# cond_sinais.net
KiCad netlist of a schematic drawn in Altium Designer
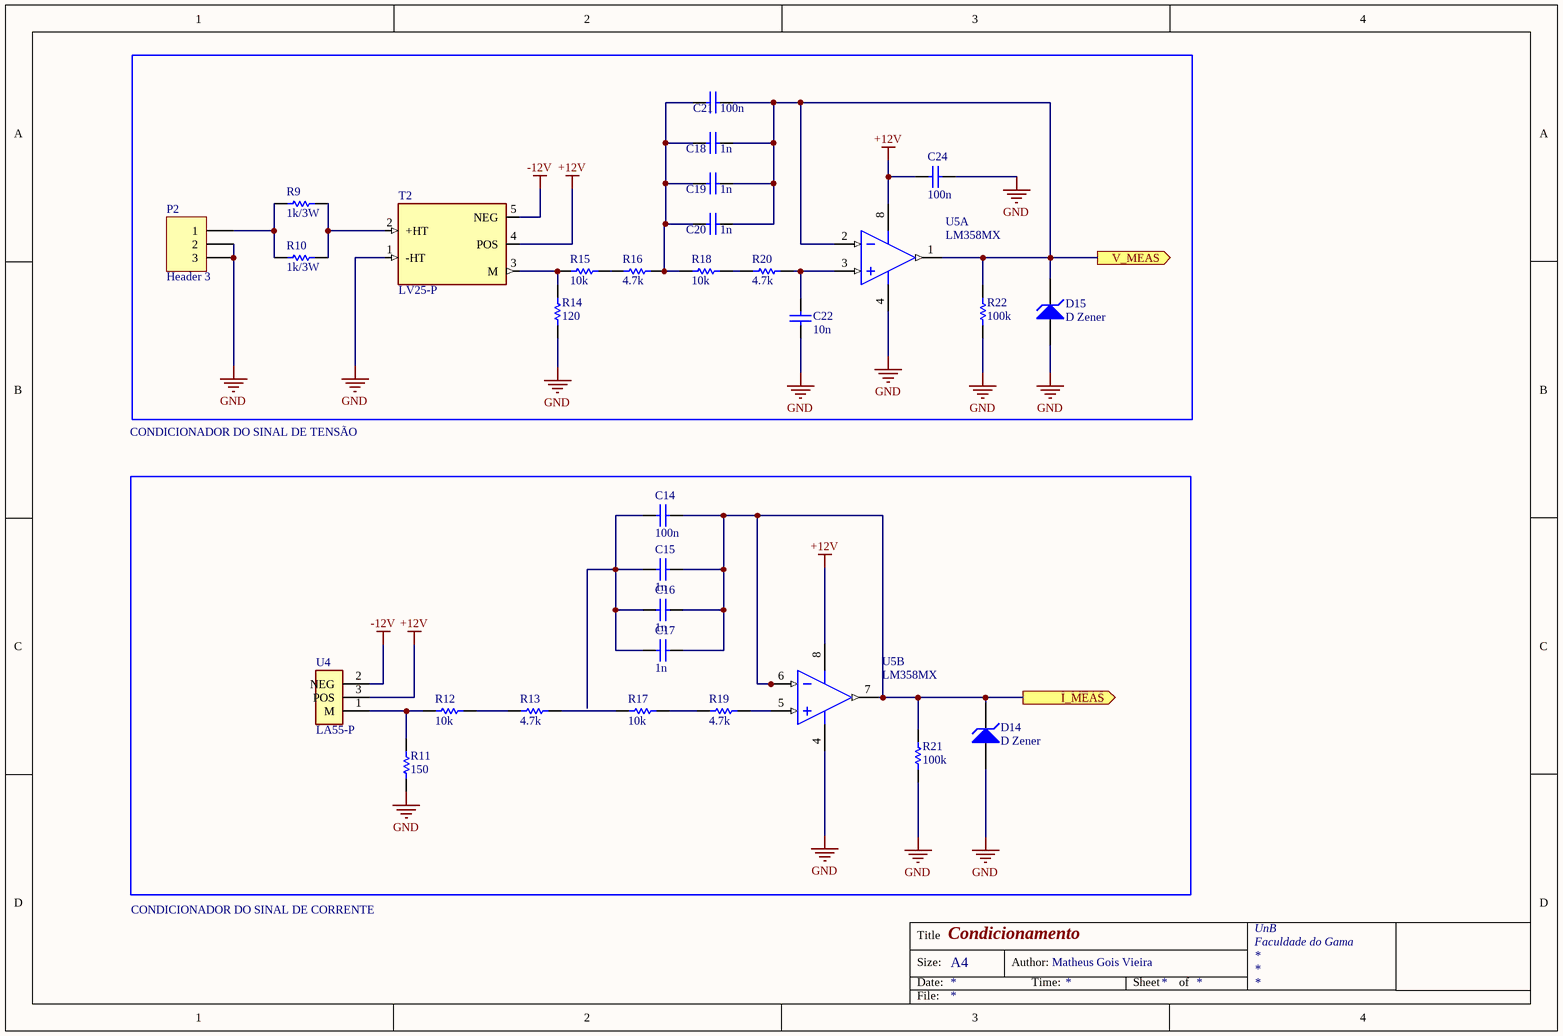
[diagram p0: cond_sinais.SchDoc]

(export (version "E")
  (design (tool "Eeschema 10.0.6"))
  (components
    (comp (ref "C14")
      (value "100n")
      (footprint "C0603[0201]")
      (description "CAP CER 10000PF 50V X7R 0603")
      (fields (field (name "MANUFACTURER PART NUMBER") "C0603C103K5RACTU") (field (name "TOLERANCE") "10%"))
      (libsource (lib "Basic Library") (part "C"))
    )
    (comp (ref "C15")
      (value "1n")
      (footprint "C0603[0201]")
      (description "Cap Ceramic 0.001uF 50V X7R 10% SMD 0603 125C T/R")
      (fields (field (name "MANUFACTURER PART NUMBER") "C0603C102K5RACTU") (field (name "TOLERANCE") "10%"))
      (libsource (lib "Basic Library") (part "C"))
    )
    (comp (ref "C16")
      (value "1n")
      (footprint "C0603[0201]")
      (description "Cap Ceramic 0.001uF 50V X7R 10% SMD 0603 125C T/R")
      (fields (field (name "MANUFACTURER PART NUMBER") "C0603C102K5RACTU") (field (name "TOLERANCE") "10%"))
      (libsource (lib "Basic Library") (part "C"))
    )
    (comp (ref "C17")
      (value "1n")
      (footprint "C0603[0201]")
      (description "Cap Ceramic 0.001uF 50V X7R 10% SMD 0603 125C T/R")
      (fields (field (name "MANUFACTURER PART NUMBER") "C0603C102K5RACTU") (field (name "TOLERANCE") "10%"))
      (libsource (lib "Basic Library") (part "C"))
    )
    (comp (ref "C18")
      (value "1n")
      (footprint "C0603[0201]")
      (description "Cap Ceramic 0.001uF 50V X7R 10% SMD 0603 125C T/R")
      (fields (field (name "MANUFACTURER PART NUMBER") "C0603C102K5RACTU") (field (name "TOLERANCE") "10%"))
      (libsource (lib "Basic Library") (part "C"))
    )
    (comp (ref "C19")
      (value "1n")
      (footprint "C0603[0201]")
      (description "Cap Ceramic 0.001uF 50V X7R 10% SMD 0603 125C T/R")
      (fields (field (name "MANUFACTURER PART NUMBER") "C0603C102K5RACTU") (field (name "TOLERANCE") "10%"))
      (libsource (lib "Basic Library") (part "C"))
    )
    (comp (ref "C20")
      (value "1n")
      (footprint "C0603[0201]")
      (description "Cap Ceramic 0.001uF 50V X7R 10% SMD 0603 125C T/R")
      (fields (field (name "MANUFACTURER PART NUMBER") "C0603C102K5RACTU") (field (name "TOLERANCE") "10%"))
      (libsource (lib "Basic Library") (part "C"))
    )
    (comp (ref "C21")
      (value "100n")
      (footprint "C0603[0201]")
      (description "CAP CER 10000PF 50V X7R 0603")
      (fields (field (name "MANUFACTURER PART NUMBER") "C0603C103K5RACTU") (field (name "TOLERANCE") "10%"))
      (libsource (lib "Basic Library") (part "C"))
    )
    (comp (ref "C22")
      (value "10n")
      (footprint "C0603[0201]")
      (description "CAP CER 10000PF 50V X7R 0603")
      (fields (field (name "MANUFACTURER PART NUMBER") "C0603C103K5RACTU") (field (name "TOLERANCE") "10%"))
      (libsource (lib "Basic Library") (part "C"))
    )
    (comp (ref "C24")
      (value "100n")
      (footprint "C0603[0201]")
      (description "贴片陶瓷电容 0.1uF ±10% 50V X7R 0603")
      (fields (field (name "MANUFACTURER PART NUMBER") "C0603C104K5RACTU") (field (name "TOLERANCE") "10%"))
      (libsource (lib "Basic Library") (part "C"))
    )
    (comp (ref "D14")
      (value "D Zener")
      (footprint "DIODE-SIGNAL")
      (description "Diode Zener Single 9.1V 5% 500mW 2-Pin(1+Tab) Power Mite T/R")
      (fields (field (name "MANUFACTURER PART NUMBER") "1PMT5924BT1G") (field (name "TOLERANCE") "5%"))
      (libsource (lib "Basic Library") (part "D Zener"))
    )
    (comp (ref "D15")
      (value "D Zener")
      (footprint "DIODE-SIGNAL")
      (description "Diode Zener Single 9.1V 5% 500mW 2-Pin(1+Tab) Power Mite T/R")
      (fields (field (name "MANUFACTURER PART NUMBER") "1PMT5924BT1G") (field (name "TOLERANCE") "5%"))
      (libsource (lib "Basic Library") (part "D Zener"))
    )
    (comp (ref "P2")
      (value "Header 3")
      (footprint "HDR1X3")
      (description "Header, 3-Pin")
      (fields (field (name "PUBLISHER") "Altium Limited"))
      (libsource (lib "Miscellaneous Connectors") (part "Header 3"))
    )
    (comp (ref "R9")
      (value "1k/3W")
      (footprint "R1005[0402]")
      (description "Res Thick Film 2512 1K Ohm 5% 3W ±100ppm/C Pad SMD T/R")
      (fields (field (name "MANUFACTURER PART NUMBER") "35221K0JT") (field (name "TOLERANCE") "5%"))
      (libsource (lib "Basic Library") (part "R"))
    )
    (comp (ref "R10")
      (value "1k/3W")
      (footprint "R1005[0402]")
      (description "Res Thick Film 2512 1K Ohm 5% 3W ±100ppm/C Pad SMD T/R")
      (fields (field (name "MANUFACTURER PART NUMBER") "35221K0JT") (field (name "TOLERANCE") "5%"))
      (libsource (lib "Basic Library") (part "R"))
    )
    (comp (ref "R11")
      (value "150")
      (footprint "R1005[0402]")
      (description "贴片电阻 150Ω ±1% 1/4W ±100ppm/℃ 1206")
      (fields (field (name "MANUFACTURER PART NUMBER") "ERJ-8ENF1500V") (field (name "TOLERANCE") "1%"))
      (libsource (lib "Basic Library") (part "R"))
    )
    (comp (ref "R12")
      (value "10k")
      (footprint "R1608[0603]")
      (description "Res, 10K, 0.01%, 0.25W, 1206, Metal Foil")
      (fields (field (name "MANUFACTURER PART NUMBER") "Y163010K0000T9R") (field (name "TOLERANCE") "0.01%"))
      (libsource (lib "Basic Library") (part "R"))
    )
    (comp (ref "R13")
      (value "4.7k")
      (footprint "R1005[0402]")
      (description "Res Thick Film 1206 4.7K Ohm 5% 1/4W ±200ppm/°C Molded SMD Punched Carrier T/R")
      (fields (field (name "MANUFACTURER PART NUMBER") "ERJ-8GEYJ472V") (field (name "TOLERANCE") "5%"))
      (libsource (lib "Basic Library") (part "R"))
    )
    (comp (ref "R14")
      (value "120")
      (footprint "R1005[0402]")
      (description "Resistor Thick Film 1206 120 Ohm 5% 1/4W 200ppm/C Molded SMD Punched Carrier T/R")
      (fields (field (name "MANUFACTURER PART NUMBER") "ERJ-8GEYJ121V") (field (name "TOLERANCE") "5%"))
      (libsource (lib "Basic Library") (part "R"))
    )
    (comp (ref "R15")
      (value "10k")
      (footprint "R1608[0603]")
      (description "Res, 10K, 0.01%, 0.25W, 1206, Metal Foil")
      (fields (field (name "MANUFACTURER PART NUMBER") "Y163010K0000T9R") (field (name "TOLERANCE") "0.01%"))
      (libsource (lib "Basic Library") (part "R"))
    )
    (comp (ref "R16")
      (value "4.7k")
      (footprint "R1005[0402]")
      (description "Res Thick Film 1206 4.7K Ohm 5% 1/4W ±200ppm/°C Molded SMD Punched Carrier T/R")
      (fields (field (name "MANUFACTURER PART NUMBER") "ERJ-8GEYJ472V") (field (name "TOLERANCE") "5%"))
      (libsource (lib "Basic Library") (part "R"))
    )
    (comp (ref "R17")
      (value "10k")
      (footprint "R1005[0402]")
      (description "Res, 10K, 0.01%, 0.25W, 1206, Metal Foil")
      (fields (field (name "MANUFACTURER PART NUMBER") "Y163010K0000T9R") (field (name "TOLERANCE") "0.01%"))
      (libsource (lib "Basic Library") (part "R"))
    )
    (comp (ref "R18")
      (value "10k")
      (footprint "R1005[0402]")
      (description "Res, 10K, 0.01%, 0.25W, 1206, Metal Foil")
      (fields (field (name "MANUFACTURER PART NUMBER") "Y163010K0000T9R") (field (name "TOLERANCE") "0.01%"))
      (libsource (lib "Basic Library") (part "R"))
    )
    (comp (ref "R19")
      (value "4.7k")
      (footprint "R1005[0402]")
      (description "Res Thick Film 1206 4.7K Ohm 5% 1/4W ±200ppm/°C Molded SMD Punched Carrier T/R")
      (fields (field (name "MANUFACTURER PART NUMBER") "ERJ-8GEYJ472V") (field (name "TOLERANCE") "5%"))
      (libsource (lib "Basic Library") (part "R"))
    )
    (comp (ref "R20")
      (value "4.7k")
      (footprint "R1005[0402]")
      (description "Res Thick Film 1206 4.7K Ohm 5% 1/4W ±200ppm/°C Molded SMD Punched Carrier T/R")
      (fields (field (name "MANUFACTURER PART NUMBER") "ERJ-8GEYJ472V") (field (name "TOLERANCE") "5%"))
      (libsource (lib "Basic Library") (part "R"))
    )
    (comp (ref "R21")
      (value "100k")
      (footprint "R1005[0402]")
      (description "贴片电阻 100KΩ ±1% 1/4W ±100ppm/℃ 1206")
      (fields (field (name "MANUFACTURER PART NUMBER") "ERJ-8ENF1003V") (field (name "TOLERANCE") "1%"))
      (libsource (lib "Basic Library") (part "R"))
    )
    (comp (ref "R22")
      (value "100k")
      (footprint "R1005[0402]")
      (description "贴片电阻 100KΩ ±1% 1/4W ±100ppm/℃ 1206")
      (fields (field (name "MANUFACTURER PART NUMBER") "ERJ-8ENF1003V") (field (name "TOLERANCE") "1%"))
      (libsource (lib "Basic Library") (part "R"))
    )
    (comp (ref "T2")
      (value "LV25-P")
      (footprint "XDCR_LV25-P")
      (description "Hall Effect Voltage Transducer")
      (fields (field (name "DIGI-KEY_PART_NUMBER") "398-1019-ND") (field (name "MF") "LEM USA Inc."))
      (libsource (lib "LV25-P") (part "LV25-P"))
    )
    (comp (ref "U4")
      (value "LA55-P")
      (footprint "XDCR_LA55-P")
      (description "Current Sensor 50A 1 Channel Hall Effect, Closed Loop Bidirectional Module, Single Pass Through")
      (fields (field (name "MP") "LA 55-P") (field (name "MF") "LEM USA"))
      (libsource (lib "LA55-P") (part "LA55-P"))
    )
    (comp (ref "U5")
      (value "LM358MX")
      (footprint "M08A_N")
      (description "LM358 Series 7 mV Input Offset Dual Operational Amplifier - SOIC-8")
      (fields (field (name "MANUFACTURER") "National Semiconductor"))
      (libsource (lib "National Semiconductor Amplifier") (part "LM358MX"))
    )
  )
  (nets
    (net (code "1") (name "+12V") (class "Default")
      (node (ref "C24") (pin "2") (pinfunction "2_2") (pintype "passive"))
      (node (ref "T2") (pin "4") (pinfunction "POS_4") (pintype "power_in"))
      (node (ref "U4") (pin "3") (pinfunction "POS_3") (pintype "power_in"))
      (node (ref "U5") (pin "8") (pinfunction "V+_8") (pintype "power_in"))
    )
    (net (code "2") (name "-12V") (class "Default")
      (node (ref "T2") (pin "5") (pinfunction "NEG_5") (pintype "power_in"))
      (node (ref "U4") (pin "2") (pinfunction "NEG_2") (pintype "power_in"))
    )
    (net (code "3") (name "/I_MEAS") (class "Default")
      (node (ref "C14") (pin "2") (pinfunction "2_2") (pintype "passive"))
      (node (ref "C15") (pin "2") (pinfunction "2_2") (pintype "passive"))
      (node (ref "C16") (pin "2") (pinfunction "2_2") (pintype "passive"))
      (node (ref "C17") (pin "2") (pinfunction "2_2") (pintype "passive"))
      (node (ref "D14") (pin "2") (pinfunction "K_2") (pintype "passive"))
      (node (ref "R21") (pin "2") (pinfunction "2_2") (pintype "passive"))
      (node (ref "U5") (pin "6") (pinfunction "INB-_6") (pintype "input"))
      (node (ref "U5") (pin "7") (pinfunction "OUTB_7") (pintype "output"))
    )
    (net (code "4") (name "/V_MEAS") (class "Default")
      (node (ref "C18") (pin "2") (pinfunction "2_2") (pintype "passive"))
      (node (ref "C19") (pin "2") (pinfunction "2_2") (pintype "passive"))
      (node (ref "C20") (pin "2") (pinfunction "2_2") (pintype "passive"))
      (node (ref "C21") (pin "2") (pinfunction "2_2") (pintype "passive"))
      (node (ref "D15") (pin "2") (pinfunction "K_2") (pintype "passive"))
      (node (ref "R22") (pin "2") (pinfunction "2_2") (pintype "passive"))
      (node (ref "U5") (pin "1") (pinfunction "OUTA_1") (pintype "output"))
      (node (ref "U5") (pin "2") (pinfunction "INA-_2") (pintype "input"))
    )
    (net (code "5") (name "GND") (class "Default")
      (node (ref "C22") (pin "1") (pinfunction "1_1") (pintype "passive"))
      (node (ref "C24") (pin "1") (pinfunction "1_1") (pintype "passive"))
      (node (ref "D14") (pin "1") (pinfunction "A_1") (pintype "passive"))
      (node (ref "D15") (pin "1") (pinfunction "A_1") (pintype "passive"))
      (node (ref "P2") (pin "2") (pinfunction "2_2") (pintype "passive"))
      (node (ref "P2") (pin "3") (pinfunction "3_3") (pintype "passive"))
      (node (ref "R11") (pin "1") (pinfunction "1_1") (pintype "passive"))
      (node (ref "R14") (pin "1") (pinfunction "1_1") (pintype "passive"))
      (node (ref "R21") (pin "1") (pinfunction "1_1") (pintype "passive"))
      (node (ref "R22") (pin "1") (pinfunction "1_1") (pintype "passive"))
      (node (ref "T2") (pin "1") (pinfunction "-HT_1") (pintype "input"))
      (node (ref "U5") (pin "4") (pinfunction "GND_4") (pintype "power_in"))
    )
    (net (code "6") (name "Net-(C14-Pad1)") (class "Default")
      (node (ref "C14") (pin "1") (pinfunction "1_1") (pintype "passive"))
      (node (ref "C15") (pin "1") (pinfunction "1_1") (pintype "passive"))
      (node (ref "C16") (pin "1") (pinfunction "1_1") (pintype "passive"))
      (node (ref "C17") (pin "1") (pinfunction "1_1") (pintype "passive"))
    )
    (net (code "7") (name "Net-(C18-Pad1)") (class "Default")
      (node (ref "C18") (pin "1") (pinfunction "1_1") (pintype "passive"))
      (node (ref "C19") (pin "1") (pinfunction "1_1") (pintype "passive"))
      (node (ref "C20") (pin "1") (pinfunction "1_1") (pintype "passive"))
      (node (ref "C21") (pin "1") (pinfunction "1_1") (pintype "passive"))
      (node (ref "R16") (pin "2") (pinfunction "2_2") (pintype "passive"))
      (node (ref "R18") (pin "1") (pinfunction "1_1") (pintype "passive"))
    )
    (net (code "8") (name "Net-(P2-Pad1)") (class "Default")
      (node (ref "P2") (pin "1") (pinfunction "1_1") (pintype "passive"))
      (node (ref "R10") (pin "1") (pinfunction "1_1") (pintype "passive"))
      (node (ref "R9") (pin "1") (pinfunction "1_1") (pintype "passive"))
    )
    (net (code "9") (name "Net-(R12-Pad2)") (class "Default")
      (node (ref "R12") (pin "2") (pinfunction "2_2") (pintype "passive"))
      (node (ref "R13") (pin "1") (pinfunction "1_1") (pintype "passive"))
    )
    (net (code "10") (name "Net-(R13-Pad2)") (class "Default")
      (node (ref "R13") (pin "2") (pinfunction "2_2") (pintype "passive"))
      (node (ref "R17") (pin "1") (pinfunction "1_1") (pintype "passive"))
    )
    (net (code "11") (name "Net-(R15-Pad2)") (class "Default")
      (node (ref "R15") (pin "2") (pinfunction "2_2") (pintype "passive"))
      (node (ref "R16") (pin "1") (pinfunction "1_1") (pintype "passive"))
    )
    (net (code "12") (name "Net-(R17-Pad2)") (class "Default")
      (node (ref "R17") (pin "2") (pinfunction "2_2") (pintype "passive"))
      (node (ref "R19") (pin "1") (pinfunction "1_1") (pintype "passive"))
    )
    (net (code "13") (name "Net-(R18-Pad2)") (class "Default")
      (node (ref "R18") (pin "2") (pinfunction "2_2") (pintype "passive"))
      (node (ref "R20") (pin "1") (pinfunction "1_1") (pintype "passive"))
    )
    (net (code "14") (name "Net-(T2-+HT)") (class "Default")
      (node (ref "R10") (pin "2") (pinfunction "2_2") (pintype "passive"))
      (node (ref "R9") (pin "2") (pinfunction "2_2") (pintype "passive"))
      (node (ref "T2") (pin "2") (pinfunction "+HT_2") (pintype "input"))
    )
    (net (code "15") (name "Net-(T2-M)") (class "Default")
      (node (ref "R14") (pin "2") (pinfunction "2_2") (pintype "passive"))
      (node (ref "R15") (pin "1") (pinfunction "1_1") (pintype "passive"))
      (node (ref "T2") (pin "3") (pinfunction "M_3") (pintype "output"))
    )
    (net (code "16") (name "Net-(U4-M)") (class "Default")
      (node (ref "R11") (pin "2") (pinfunction "2_2") (pintype "passive"))
      (node (ref "R12") (pin "1") (pinfunction "1_1") (pintype "passive"))
      (node (ref "U4") (pin "1") (pinfunction "M_1") (pintype "power_in"))
    )
    (net (code "17") (name "Net-(U5A-INA+)") (class "Default")
      (node (ref "C22") (pin "2") (pinfunction "2_2") (pintype "passive"))
      (node (ref "R20") (pin "2") (pinfunction "2_2") (pintype "passive"))
      (node (ref "U5") (pin "3") (pinfunction "INA+_3") (pintype "input"))
    )
    (net (code "18") (name "Net-(U5B-INB+)") (class "Default")
      (node (ref "R19") (pin "2") (pinfunction "2_2") (pintype "passive"))
      (node (ref "U5") (pin "5") (pinfunction "INB+_5") (pintype "input"))
    )
  )
)
